# Sonar.net
KiCad netlist of a schematic drawn in Altium Designer
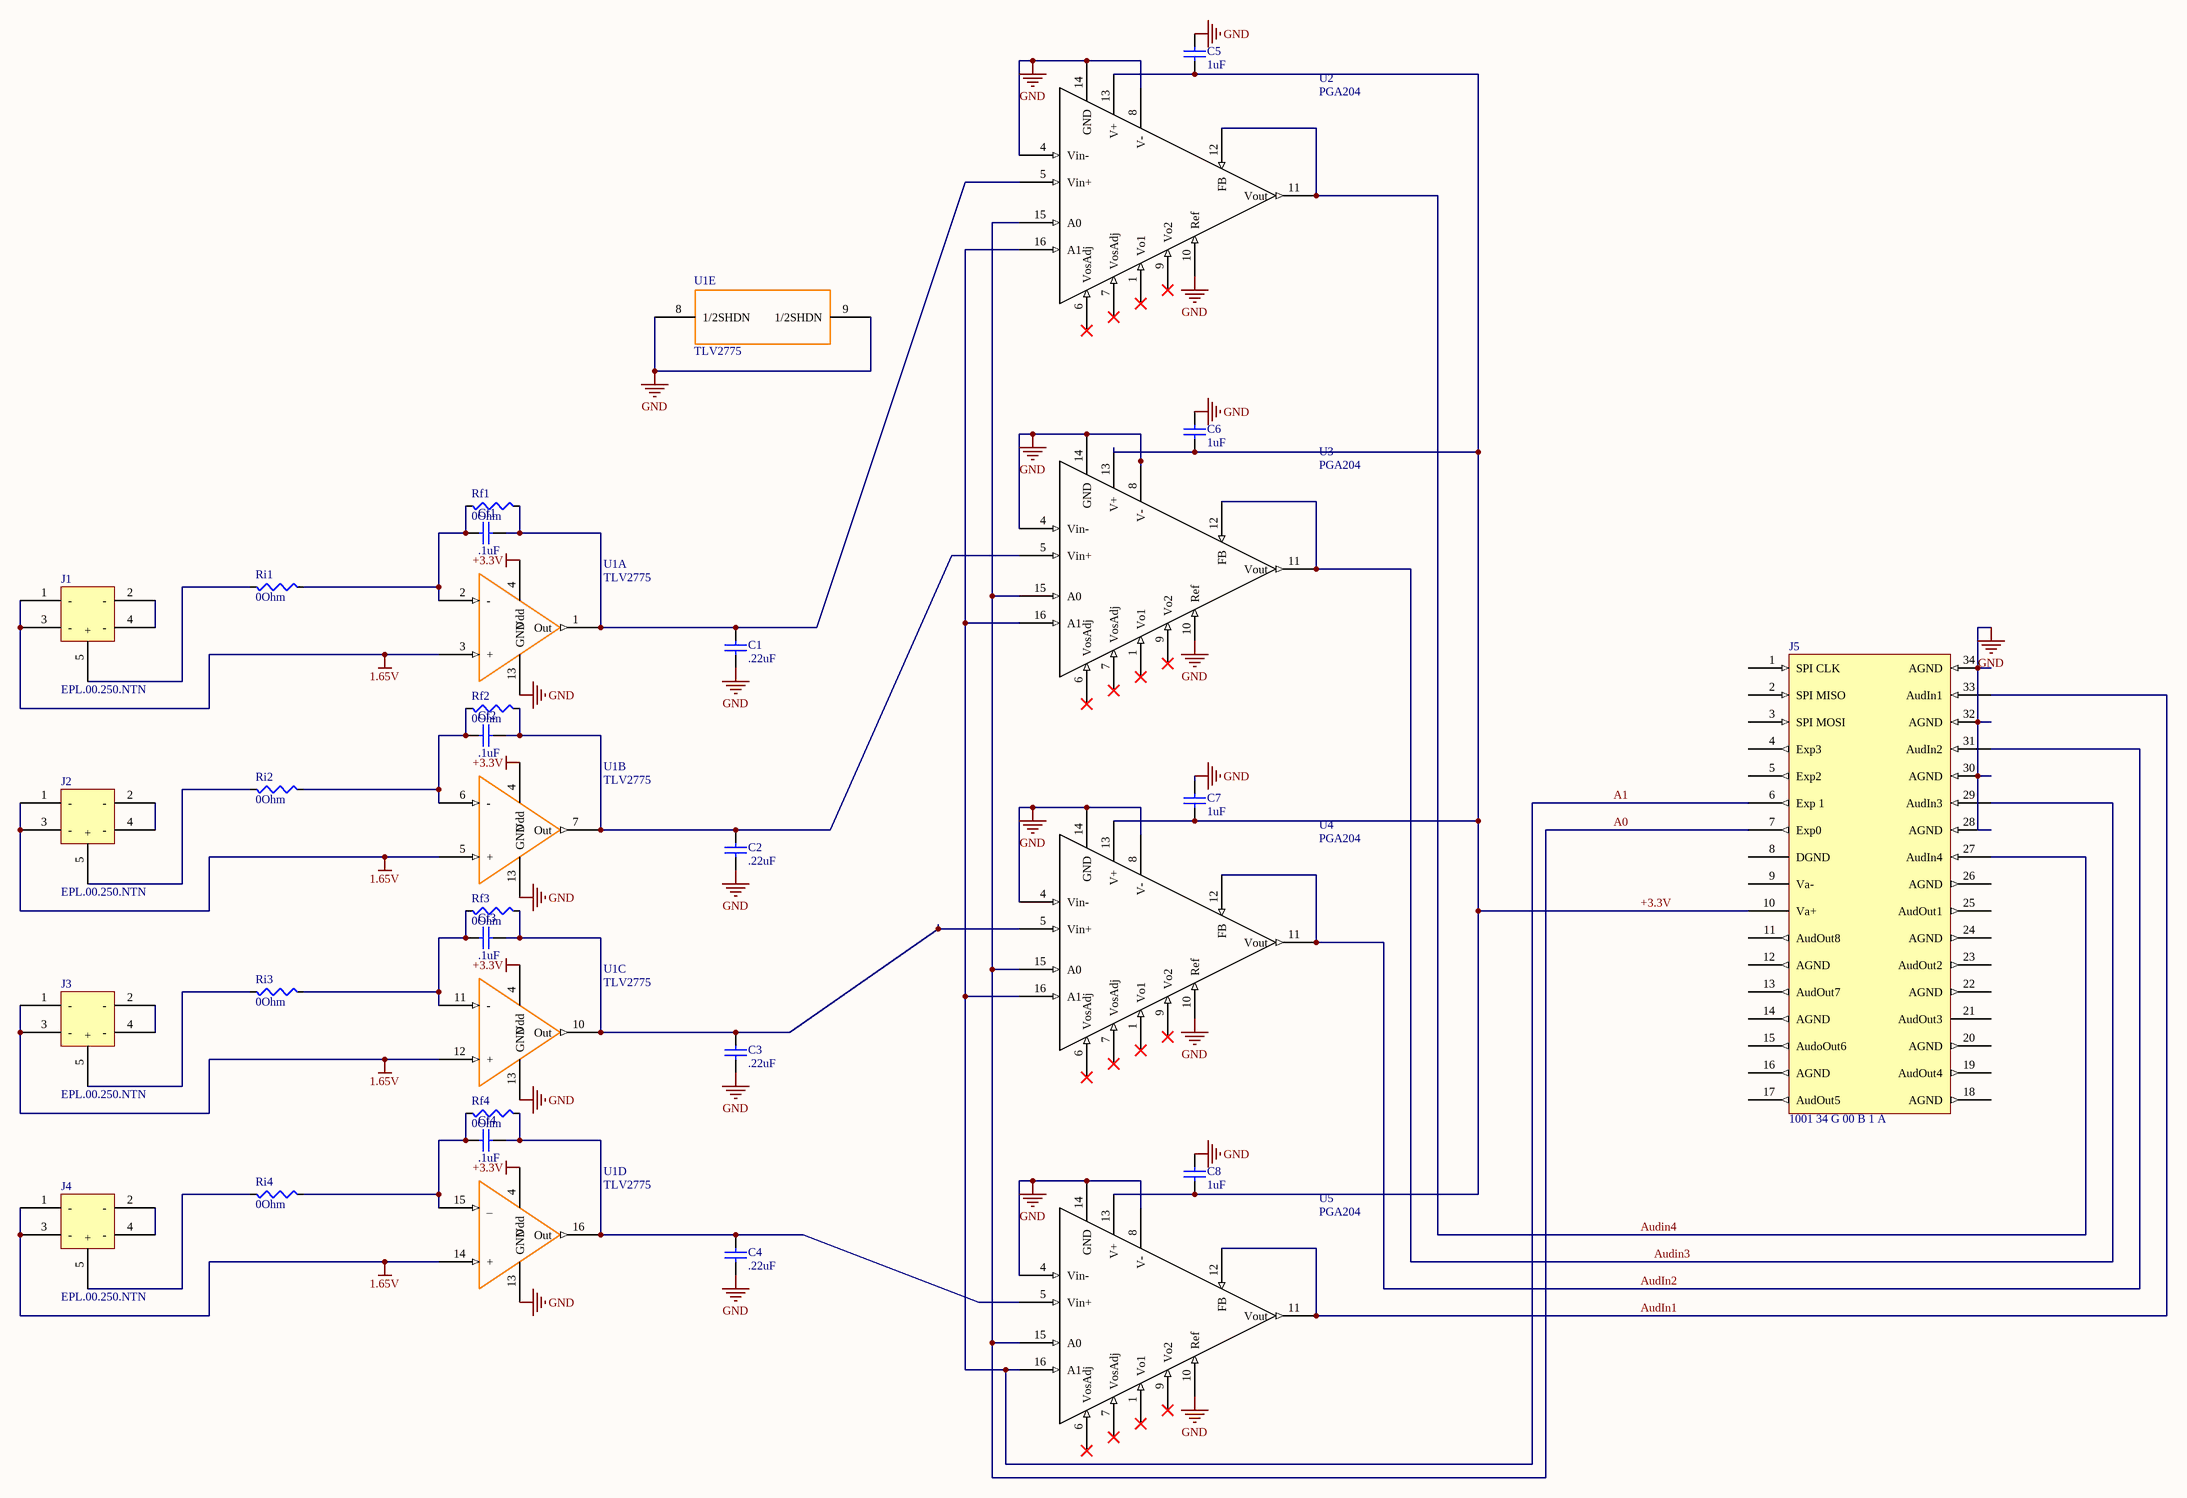
[diagram p0: Sonar.SchDoc]

(export (version "E")
  (design (tool "Eeschema 10.0.6"))
  (components
    (comp (ref "C1")
      (value ".22uF")
      (footprint "PassiveComponents:0805 (2012) Capacitor")
      (description "Capacitor")
      (libsource (lib "PassiveComponents") (part "Capacitor (non-polarized)"))
    )
    (comp (ref "C2")
      (value ".22uF")
      (footprint "PassiveComponents:0805 (2012) Capacitor")
      (description "Capacitor")
      (libsource (lib "PassiveComponents") (part "Capacitor (non-polarized)"))
    )
    (comp (ref "C3")
      (value ".22uF")
      (footprint "PassiveComponents:0805 (2012) Capacitor")
      (description "Capacitor")
      (libsource (lib "PassiveComponents") (part "Capacitor (non-polarized)"))
    )
    (comp (ref "C4")
      (value ".22uF")
      (footprint "PassiveComponents:0805 (2012) Capacitor")
      (description "Capacitor")
      (libsource (lib "PassiveComponents") (part "Capacitor (non-polarized)"))
    )
    (comp (ref "C5")
      (value "1uF")
      (footprint "PassiveComponents:0805 (2012) Capacitor")
      (description "Capacitor")
      (libsource (lib "PassiveComponents") (part "Capacitor (non-polarized)"))
    )
    (comp (ref "C6")
      (value "1uF")
      (footprint "PassiveComponents:0805 (2012) Capacitor")
      (description "Capacitor")
      (libsource (lib "PassiveComponents") (part "Capacitor (non-polarized)"))
    )
    (comp (ref "C7")
      (value "1uF")
      (footprint "PassiveComponents:0805 (2012) Capacitor")
      (description "Capacitor")
      (libsource (lib "PassiveComponents") (part "Capacitor (non-polarized)"))
    )
    (comp (ref "C8")
      (value "1uF")
      (footprint "PassiveComponents:0805 (2012) Capacitor")
      (description "Capacitor")
      (libsource (lib "PassiveComponents") (part "Capacitor (non-polarized)"))
    )
    (comp (ref "Cf1")
      (value ".1uF")
      (footprint "PassiveComponents:0805 (2012) Capacitor")
      (description "Capacitor")
      (libsource (lib "PassiveComponents") (part "Capacitor (non-polarized)"))
    )
    (comp (ref "Cf2")
      (value ".1uF")
      (footprint "PassiveComponents:0805 (2012) Capacitor")
      (description "Capacitor")
      (libsource (lib "PassiveComponents") (part "Capacitor (non-polarized)"))
    )
    (comp (ref "Cf3")
      (value ".1uF")
      (footprint "PassiveComponents:0805 (2012) Capacitor")
      (description "Capacitor")
      (libsource (lib "PassiveComponents") (part "Capacitor (non-polarized)"))
    )
    (comp (ref "Cf4")
      (value ".1uF")
      (footprint "PassiveComponents:0805 (2012) Capacitor")
      (description "Capacitor")
      (libsource (lib "PassiveComponents") (part "Capacitor (non-polarized)"))
    )
    (comp (ref "J1")
      (value "EPL.00.250.NTN")
      (footprint "EPL.00.250.NTN_1")
      (libsource (lib "Sonar") (part "EPL.00.250.NTN"))
    )
    (comp (ref "J2")
      (value "EPL.00.250.NTN")
      (footprint "EPL.00.250.NTN_1")
      (libsource (lib "Sonar") (part "EPL.00.250.NTN"))
    )
    (comp (ref "J3")
      (value "EPL.00.250.NTN")
      (footprint "EPL.00.250.NTN_1")
      (libsource (lib "Sonar") (part "EPL.00.250.NTN"))
    )
    (comp (ref "J4")
      (value "EPL.00.250.NTN")
      (footprint "EPL.00.250.NTN_1")
      (libsource (lib "Sonar") (part "EPL.00.250.NTN"))
    )
    (comp (ref "J5")
      (value "1001 34 G 00 B 1 A")
      (footprint "1001")
      (libsource (lib "Sonar") (part "1001 34 G 00 B 1 A"))
    )
    (comp (ref "Rf1")
      (value "0Ohm")
      (footprint "PassiveComponents:R 0805 (2012) RESISTOR")
      (description "Resistor")
      (libsource (lib "PassiveComponents") (part "Resistor"))
    )
    (comp (ref "Rf2")
      (value "0Ohm")
      (footprint "PassiveComponents:R 0805 (2012) RESISTOR")
      (description "Resistor")
      (libsource (lib "PassiveComponents") (part "Resistor"))
    )
    (comp (ref "Rf3")
      (value "0Ohm")
      (footprint "PassiveComponents:R 0805 (2012) RESISTOR")
      (description "Resistor")
      (libsource (lib "PassiveComponents") (part "Resistor"))
    )
    (comp (ref "Rf4")
      (value "0Ohm")
      (footprint "PassiveComponents:R 0805 (2012) RESISTOR")
      (description "Resistor")
      (libsource (lib "PassiveComponents") (part "Resistor"))
    )
    (comp (ref "Ri1")
      (value "0Ohm")
      (footprint "PassiveComponents:R 0805 (2012) RESISTOR")
      (description "Resistor")
      (libsource (lib "PassiveComponents") (part "Resistor"))
    )
    (comp (ref "Ri2")
      (value "0Ohm")
      (footprint "PassiveComponents:R 0805 (2012) RESISTOR")
      (description "Resistor")
      (libsource (lib "PassiveComponents") (part "Resistor"))
    )
    (comp (ref "Ri3")
      (value "0Ohm")
      (footprint "PassiveComponents:R 0805 (2012) RESISTOR")
      (description "Resistor")
      (libsource (lib "PassiveComponents") (part "Resistor"))
    )
    (comp (ref "Ri4")
      (value "0Ohm")
      (footprint "PassiveComponents:R 0805 (2012) RESISTOR")
      (description "Resistor")
      (libsource (lib "PassiveComponents") (part "Resistor"))
    )
    (comp (ref "U1")
      (value "TLV2775")
      (footprint "TlV2775AIPW")
      (description "2.7 V High-Slew-Rate Rail-to-Rail Output Operation Amplifer with ShutDown")
      (libsource (lib "Sonar") (part "TLV2775"))
    )
    (comp (ref "U2") (value "PGA204") (footprint "SOIC 16") (libsource (lib "Sonar") (part "PGA204")))
    (comp (ref "U3") (value "PGA204") (footprint "SOIC 16") (libsource (lib "Sonar") (part "PGA204")))
    (comp (ref "U4") (value "PGA204") (footprint "SOIC 16") (libsource (lib "Sonar") (part "PGA204")))
    (comp (ref "U5") (value "PGA204") (footprint "SOIC 16") (libsource (lib "Sonar") (part "PGA204")))
  )
  (nets
    (net (code "1") (name "+3.3V") (class "Default")
      (node (ref "C5") (pin "1") (pinfunction "1_1") (pintype "passive"))
      (node (ref "C6") (pin "1") (pinfunction "1_1") (pintype "passive"))
      (node (ref "C7") (pin "1") (pinfunction "1_1") (pintype "passive"))
      (node (ref "C8") (pin "1") (pinfunction "1_1") (pintype "passive"))
      (node (ref "J5") (pin "10") (pinfunction "Va+_10") (pintype "power_in"))
      (node (ref "U1") (pin "4") (pinfunction "Vdd_4") (pintype "power_in"))
      (node (ref "U2") (pin "13") (pinfunction "V+_13") (pintype "power_in"))
      (node (ref "U3") (pin "13") (pinfunction "V+_13") (pintype "power_in"))
      (node (ref "U4") (pin "13") (pinfunction "V+_13") (pintype "power_in"))
      (node (ref "U5") (pin "13") (pinfunction "V+_13") (pintype "power_in"))
    )
    (net (code "2") (name "/A0") (class "Default")
      (node (ref "J5") (pin "7") (pinfunction "Exp0_7") (pintype "output"))
      (node (ref "U2") (pin "15") (pinfunction "A0_15") (pintype "input"))
      (node (ref "U3") (pin "15") (pinfunction "A0_15") (pintype "input"))
      (node (ref "U4") (pin "15") (pinfunction "A0_15") (pintype "input"))
      (node (ref "U5") (pin "15") (pinfunction "A0_15") (pintype "input"))
    )
    (net (code "3") (name "/A1") (class "Default")
      (node (ref "J5") (pin "6") (pinfunction "Exp_1_6") (pintype "output"))
      (node (ref "U2") (pin "16") (pinfunction "A1_16") (pintype "input"))
      (node (ref "U3") (pin "16") (pinfunction "A1_16") (pintype "input"))
      (node (ref "U4") (pin "16") (pinfunction "A1_16") (pintype "input"))
      (node (ref "U5") (pin "16") (pinfunction "A1_16") (pintype "input"))
    )
    (net (code "4") (name "/AudIn1") (class "Default")
      (node (ref "J5") (pin "33") (pinfunction "AudIn1_33") (pintype "input"))
      (node (ref "U5") (pin "11") (pinfunction "Vout_11") (pintype "output"))
      (node (ref "U5") (pin "12") (pinfunction "FB_12") (pintype "input"))
    )
    (net (code "5") (name "/AudIn2") (class "Default")
      (node (ref "J5") (pin "31") (pinfunction "AudIn2_31") (pintype "input"))
      (node (ref "U4") (pin "11") (pinfunction "Vout_11") (pintype "output"))
      (node (ref "U4") (pin "12") (pinfunction "FB_12") (pintype "input"))
    )
    (net (code "6") (name "/Audin3") (class "Default")
      (node (ref "J5") (pin "29") (pinfunction "AudIn3_29") (pintype "input"))
      (node (ref "U3") (pin "11") (pinfunction "Vout_11") (pintype "output"))
      (node (ref "U3") (pin "12") (pinfunction "FB_12") (pintype "input"))
    )
    (net (code "7") (name "/Audin4") (class "Default")
      (node (ref "J5") (pin "27") (pinfunction "AudIn4_27") (pintype "input"))
      (node (ref "U2") (pin "11") (pinfunction "Vout_11") (pintype "output"))
      (node (ref "U2") (pin "12") (pinfunction "FB_12") (pintype "input"))
    )
    (net (code "8") (name "1.65V") (class "Default")
      (node (ref "J1") (pin "1") (pinfunction "-_1") (pintype "passive"))
      (node (ref "J1") (pin "3") (pinfunction "-_3") (pintype "passive"))
      (node (ref "J2") (pin "1") (pinfunction "-_1") (pintype "passive"))
      (node (ref "J2") (pin "3") (pinfunction "-_3") (pintype "passive"))
      (node (ref "J3") (pin "1") (pinfunction "-_1") (pintype "passive"))
      (node (ref "J3") (pin "3") (pinfunction "-_3") (pintype "passive"))
      (node (ref "J4") (pin "1") (pinfunction "-_1") (pintype "passive"))
      (node (ref "J4") (pin "3") (pinfunction "-_3") (pintype "passive"))
      (node (ref "U1") (pin "12") (pinfunction "+_12") (pintype "input"))
      (node (ref "U1") (pin "14") (pinfunction "+_14") (pintype "input"))
      (node (ref "U1") (pin "3") (pinfunction "+_3") (pintype "input"))
      (node (ref "U1") (pin "5") (pinfunction "+_5") (pintype "input"))
    )
    (net (code "9") (name "GND") (class "Default")
      (node (ref "C1") (pin "1") (pinfunction "1_1") (pintype "passive"))
      (node (ref "C2") (pin "1") (pinfunction "1_1") (pintype "passive"))
      (node (ref "C3") (pin "1") (pinfunction "1_1") (pintype "passive"))
      (node (ref "C4") (pin "1") (pinfunction "1_1") (pintype "passive"))
      (node (ref "C5") (pin "2") (pinfunction "2_2") (pintype "passive"))
      (node (ref "C6") (pin "2") (pinfunction "2_2") (pintype "passive"))
      (node (ref "C7") (pin "2") (pinfunction "2_2") (pintype "passive"))
      (node (ref "C8") (pin "2") (pinfunction "2_2") (pintype "passive"))
      (node (ref "J5") (pin "28") (pinfunction "AGND_28") (pintype "input"))
      (node (ref "J5") (pin "30") (pinfunction "AGND_30") (pintype "input"))
      (node (ref "J5") (pin "32") (pinfunction "AGND_32") (pintype "input"))
      (node (ref "J5") (pin "34") (pinfunction "AGND_34") (pintype "input"))
      (node (ref "U1") (pin "13") (pinfunction "GND_13") (pintype "power_in"))
      (node (ref "U1") (pin "8") (pinfunction "1/2SHDN_8") (pintype "power_in"))
      (node (ref "U1") (pin "9") (pinfunction "1/2SHDN_9") (pintype "power_in"))
      (node (ref "U2") (pin "10") (pinfunction "Ref_10") (pintype "input"))
      (node (ref "U2") (pin "14") (pinfunction "GND_14") (pintype "power_in"))
      (node (ref "U2") (pin "4") (pinfunction "Vin-_4") (pintype "input"))
      (node (ref "U2") (pin "8") (pinfunction "V-_8") (pintype "power_in"))
      (node (ref "U3") (pin "14") (pinfunction "GND_14") (pintype "power_in"))
      (node (ref "U3") (pin "4") (pinfunction "Vin-_4") (pintype "input"))
      (node (ref "U3") (pin "8") (pinfunction "V-_8") (pintype "power_in"))
      (node (ref "U4") (pin "14") (pinfunction "GND_14") (pintype "power_in"))
      (node (ref "U4") (pin "4") (pinfunction "Vin-_4") (pintype "input"))
      (node (ref "U4") (pin "8") (pinfunction "V-_8") (pintype "power_in"))
      (node (ref "U5") (pin "10") (pinfunction "Ref_10") (pintype "input"))
      (node (ref "U5") (pin "14") (pinfunction "GND_14") (pintype "power_in"))
      (node (ref "U5") (pin "4") (pinfunction "Vin-_4") (pintype "input"))
      (node (ref "U5") (pin "8") (pinfunction "V-_8") (pintype "power_in"))
    )
    (net (code "10") (name "Net-(J1-+)") (class "Default")
      (node (ref "J1") (pin "5") (pinfunction "+_5") (pintype "passive"))
      (node (ref "Ri1") (pin "1") (pinfunction "1_1") (pintype "passive"))
    )
    (net (code "11") (name "Net-(J1---Pad2)") (class "Default")
      (node (ref "J1") (pin "2") (pinfunction "-_2") (pintype "passive"))
      (node (ref "J1") (pin "4") (pinfunction "-_4") (pintype "passive"))
    )
    (net (code "12") (name "Net-(J2-+)") (class "Default")
      (node (ref "J2") (pin "5") (pinfunction "+_5") (pintype "passive"))
      (node (ref "Ri2") (pin "1") (pinfunction "1_1") (pintype "passive"))
    )
    (net (code "13") (name "Net-(J2---Pad2)") (class "Default")
      (node (ref "J2") (pin "2") (pinfunction "-_2") (pintype "passive"))
      (node (ref "J2") (pin "4") (pinfunction "-_4") (pintype "passive"))
    )
    (net (code "14") (name "Net-(J3-+)") (class "Default")
      (node (ref "J3") (pin "5") (pinfunction "+_5") (pintype "passive"))
      (node (ref "Ri3") (pin "1") (pinfunction "1_1") (pintype "passive"))
    )
    (net (code "15") (name "Net-(J3---Pad2)") (class "Default")
      (node (ref "J3") (pin "2") (pinfunction "-_2") (pintype "passive"))
      (node (ref "J3") (pin "4") (pinfunction "-_4") (pintype "passive"))
    )
    (net (code "16") (name "Net-(J4-+)") (class "Default")
      (node (ref "J4") (pin "5") (pinfunction "+_5") (pintype "passive"))
      (node (ref "Ri4") (pin "1") (pinfunction "1_1") (pintype "passive"))
    )
    (net (code "17") (name "Net-(J4---Pad2)") (class "Default")
      (node (ref "J4") (pin "2") (pinfunction "-_2") (pintype "passive"))
      (node (ref "J4") (pin "4") (pinfunction "-_4") (pintype "passive"))
    )
    (net (code "18") (name "Net-(U1A--)") (class "Default")
      (node (ref "Cf1") (pin "1") (pinfunction "1_1") (pintype "passive"))
      (node (ref "Rf1") (pin "1") (pinfunction "1_1") (pintype "passive"))
      (node (ref "Ri1") (pin "2") (pinfunction "2_2") (pintype "passive"))
      (node (ref "U1") (pin "2") (pinfunction "-_2") (pintype "input"))
    )
    (net (code "19") (name "Net-(U1A-Out)") (class "Default")
      (node (ref "C1") (pin "2") (pinfunction "2_2") (pintype "passive"))
      (node (ref "Cf1") (pin "2") (pinfunction "2_2") (pintype "passive"))
      (node (ref "Rf1") (pin "2") (pinfunction "2_2") (pintype "passive"))
      (node (ref "U1") (pin "1") (pinfunction "Out_1") (pintype "output"))
      (node (ref "U2") (pin "5") (pinfunction "Vin+_5") (pintype "input"))
    )
    (net (code "20") (name "Net-(U1B--)") (class "Default")
      (node (ref "Cf2") (pin "1") (pinfunction "1_1") (pintype "passive"))
      (node (ref "Rf2") (pin "1") (pinfunction "1_1") (pintype "passive"))
      (node (ref "Ri2") (pin "2") (pinfunction "2_2") (pintype "passive"))
      (node (ref "U1") (pin "6") (pinfunction "-_6") (pintype "input"))
    )
    (net (code "21") (name "Net-(U1B-Out)") (class "Default")
      (node (ref "C2") (pin "2") (pinfunction "2_2") (pintype "passive"))
      (node (ref "Cf2") (pin "2") (pinfunction "2_2") (pintype "passive"))
      (node (ref "Rf2") (pin "2") (pinfunction "2_2") (pintype "passive"))
      (node (ref "U1") (pin "7") (pinfunction "Out_7") (pintype "output"))
      (node (ref "U3") (pin "5") (pinfunction "Vin+_5") (pintype "input"))
    )
    (net (code "22") (name "Net-(U1C--)") (class "Default")
      (node (ref "Cf3") (pin "1") (pinfunction "1_1") (pintype "passive"))
      (node (ref "Rf3") (pin "1") (pinfunction "1_1") (pintype "passive"))
      (node (ref "Ri3") (pin "2") (pinfunction "2_2") (pintype "passive"))
      (node (ref "U1") (pin "11") (pinfunction "-_11") (pintype "input"))
    )
    (net (code "23") (name "Net-(U1C-Out)") (class "Default")
      (node (ref "C3") (pin "2") (pinfunction "2_2") (pintype "passive"))
      (node (ref "Cf3") (pin "2") (pinfunction "2_2") (pintype "passive"))
      (node (ref "Rf3") (pin "2") (pinfunction "2_2") (pintype "passive"))
      (node (ref "U1") (pin "10") (pinfunction "Out_10") (pintype "output"))
      (node (ref "U4") (pin "5") (pinfunction "Vin+_5") (pintype "input"))
    )
    (net (code "24") (name "Net-(U1D-Out)") (class "Default")
      (node (ref "C4") (pin "2") (pinfunction "2_2") (pintype "passive"))
      (node (ref "Cf4") (pin "2") (pinfunction "2_2") (pintype "passive"))
      (node (ref "Rf4") (pin "2") (pinfunction "2_2") (pintype "passive"))
      (node (ref "U1") (pin "16") (pinfunction "Out_16") (pintype "output"))
      (node (ref "U5") (pin "5") (pinfunction "Vin+_5") (pintype "input"))
    )
    (net (code "25") (name "Net-(U1D-_)") (class "Default")
      (node (ref "Cf4") (pin "1") (pinfunction "1_1") (pintype "passive"))
      (node (ref "Rf4") (pin "1") (pinfunction "1_1") (pintype "passive"))
      (node (ref "Ri4") (pin "2") (pinfunction "2_2") (pintype "passive"))
      (node (ref "U1") (pin "15") (pinfunction "__15") (pintype "input"))
    )
    (net (code "26") (name "unconnected-(J5-AGND-Pad12)") (class "Default")
      (node (ref "J5") (pin "12") (pinfunction "AGND_12") (pintype "output"))
    )
    (net (code "27") (name "unconnected-(J5-AGND-Pad14)") (class "Default")
      (node (ref "J5") (pin "14") (pinfunction "AGND_14") (pintype "output"))
    )
    (net (code "28") (name "unconnected-(J5-AGND-Pad16)") (class "Default")
      (node (ref "J5") (pin "16") (pinfunction "AGND_16") (pintype "output"))
    )
    (net (code "29") (name "unconnected-(J5-AGND-Pad18)") (class "Default")
      (node (ref "J5") (pin "18") (pinfunction "AGND_18") (pintype "output"))
    )
    (net (code "30") (name "unconnected-(J5-AGND-Pad20)") (class "Default")
      (node (ref "J5") (pin "20") (pinfunction "AGND_20") (pintype "output"))
    )
    (net (code "31") (name "unconnected-(J5-AGND-Pad22)") (class "Default")
      (node (ref "J5") (pin "22") (pinfunction "AGND_22") (pintype "output"))
    )
    (net (code "32") (name "unconnected-(J5-AGND-Pad24)") (class "Default")
      (node (ref "J5") (pin "24") (pinfunction "AGND_24") (pintype "output"))
    )
    (net (code "33") (name "unconnected-(J5-AGND-Pad26)") (class "Default")
      (node (ref "J5") (pin "26") (pinfunction "AGND_26") (pintype "output"))
    )
    (net (code "34") (name "unconnected-(J5-AudOut1-Pad25)") (class "Default")
      (node (ref "J5") (pin "25") (pinfunction "AudOut1_25") (pintype "output"))
    )
    (net (code "35") (name "unconnected-(J5-AudOut2-Pad23)") (class "Default")
      (node (ref "J5") (pin "23") (pinfunction "AudOut2_23") (pintype "output"))
    )
    (net (code "36") (name "unconnected-(J5-AudOut3-Pad21)") (class "Default")
      (node (ref "J5") (pin "21") (pinfunction "AudOut3_21") (pintype "power_in"))
    )
    (net (code "37") (name "unconnected-(J5-AudOut4-Pad19)") (class "Default")
      (node (ref "J5") (pin "19") (pinfunction "AudOut4_19") (pintype "output"))
    )
    (net (code "38") (name "unconnected-(J5-AudOut5-Pad17)") (class "Default")
      (node (ref "J5") (pin "17") (pinfunction "AudOut5_17") (pintype "output"))
    )
    (net (code "39") (name "unconnected-(J5-AudOut7-Pad13)") (class "Default")
      (node (ref "J5") (pin "13") (pinfunction "AudOut7_13") (pintype "output"))
    )
    (net (code "40") (name "unconnected-(J5-AudOut8-Pad11)") (class "Default")
      (node (ref "J5") (pin "11") (pinfunction "AudOut8_11") (pintype "output"))
    )
    (net (code "41") (name "unconnected-(J5-AudoOut6-Pad15)") (class "Default")
      (node (ref "J5") (pin "15") (pinfunction "AudoOut6_15") (pintype "output"))
    )
    (net (code "42") (name "unconnected-(J5-DGND-Pad8)") (class "Default")
      (node (ref "J5") (pin "8") (pinfunction "DGND_8") (pintype "passive"))
    )
    (net (code "43") (name "unconnected-(J5-Exp2-Pad5)") (class "Default")
      (node (ref "J5") (pin "5") (pinfunction "Exp2_5") (pintype "output"))
    )
    (net (code "44") (name "unconnected-(J5-Exp3-Pad4)") (class "Default")
      (node (ref "J5") (pin "4") (pinfunction "Exp3_4") (pintype "output"))
    )
    (net (code "45") (name "unconnected-(J5-SPI_CLK-Pad1)") (class "Default")
      (node (ref "J5") (pin "1") (pinfunction "SPI_CLK_1") (pintype "input"))
    )
    (net (code "46") (name "unconnected-(J5-SPI_MISO-Pad2)") (class "Default")
      (node (ref "J5") (pin "2") (pinfunction "SPI_MISO_2") (pintype "input"))
    )
    (net (code "47") (name "unconnected-(J5-SPI_MOSI-Pad3)") (class "Default")
      (node (ref "J5") (pin "3") (pinfunction "SPI_MOSI_3") (pintype "input"))
    )
    (net (code "48") (name "unconnected-(J5-Va--Pad9)") (class "Default")
      (node (ref "J5") (pin "9") (pinfunction "Va-_9") (pintype "power_in"))
    )
    (net (code "49") (name "unconnected-(U2-Vo1-Pad1)") (class "Default")
      (node (ref "U2") (pin "1") (pinfunction "Vo1_1") (pintype "input+no_connect"))
    )
    (net (code "50") (name "unconnected-(U2-Vo2-Pad9)") (class "Default")
      (node (ref "U2") (pin "9") (pinfunction "Vo2_9") (pintype "input+no_connect"))
    )
    (net (code "51") (name "unconnected-(U2-VosAdj-Pad6)") (class "Default")
      (node (ref "U2") (pin "6") (pinfunction "VosAdj_6") (pintype "input+no_connect"))
    )
    (net (code "52") (name "unconnected-(U2-VosAdj-Pad7)") (class "Default")
      (node (ref "U2") (pin "7") (pinfunction "VosAdj_7") (pintype "input+no_connect"))
    )
    (net (code "53") (name "unconnected-(U3-Ref-Pad10)") (class "Default")
      (node (ref "U3") (pin "10") (pinfunction "Ref_10") (pintype "input"))
    )
    (net (code "54") (name "unconnected-(U3-Vo1-Pad1)") (class "Default")
      (node (ref "U3") (pin "1") (pinfunction "Vo1_1") (pintype "input+no_connect"))
    )
    (net (code "55") (name "unconnected-(U3-Vo2-Pad9)") (class "Default")
      (node (ref "U3") (pin "9") (pinfunction "Vo2_9") (pintype "input+no_connect"))
    )
    (net (code "56") (name "unconnected-(U3-VosAdj-Pad6)") (class "Default")
      (node (ref "U3") (pin "6") (pinfunction "VosAdj_6") (pintype "input+no_connect"))
    )
    (net (code "57") (name "unconnected-(U3-VosAdj-Pad7)") (class "Default")
      (node (ref "U3") (pin "7") (pinfunction "VosAdj_7") (pintype "input+no_connect"))
    )
    (net (code "58") (name "unconnected-(U4-Ref-Pad10)") (class "Default")
      (node (ref "U4") (pin "10") (pinfunction "Ref_10") (pintype "input"))
    )
    (net (code "59") (name "unconnected-(U4-Vo1-Pad1)") (class "Default")
      (node (ref "U4") (pin "1") (pinfunction "Vo1_1") (pintype "input+no_connect"))
    )
    (net (code "60") (name "unconnected-(U4-Vo2-Pad9)") (class "Default")
      (node (ref "U4") (pin "9") (pinfunction "Vo2_9") (pintype "input+no_connect"))
    )
    (net (code "61") (name "unconnected-(U4-VosAdj-Pad6)") (class "Default")
      (node (ref "U4") (pin "6") (pinfunction "VosAdj_6") (pintype "input+no_connect"))
    )
    (net (code "62") (name "unconnected-(U4-VosAdj-Pad7)") (class "Default")
      (node (ref "U4") (pin "7") (pinfunction "VosAdj_7") (pintype "input+no_connect"))
    )
    (net (code "63") (name "unconnected-(U5-Vo1-Pad1)") (class "Default")
      (node (ref "U5") (pin "1") (pinfunction "Vo1_1") (pintype "input+no_connect"))
    )
    (net (code "64") (name "unconnected-(U5-Vo2-Pad9)") (class "Default")
      (node (ref "U5") (pin "9") (pinfunction "Vo2_9") (pintype "input+no_connect"))
    )
    (net (code "65") (name "unconnected-(U5-VosAdj-Pad6)") (class "Default")
      (node (ref "U5") (pin "6") (pinfunction "VosAdj_6") (pintype "input+no_connect"))
    )
    (net (code "66") (name "unconnected-(U5-VosAdj-Pad7)") (class "Default")
      (node (ref "U5") (pin "7") (pinfunction "VosAdj_7") (pintype "input+no_connect"))
    )
  )
)
